# 436-300-001_Main_Power_Enclosure.net
KiCad netlist of a schematic drawn in EAGLE
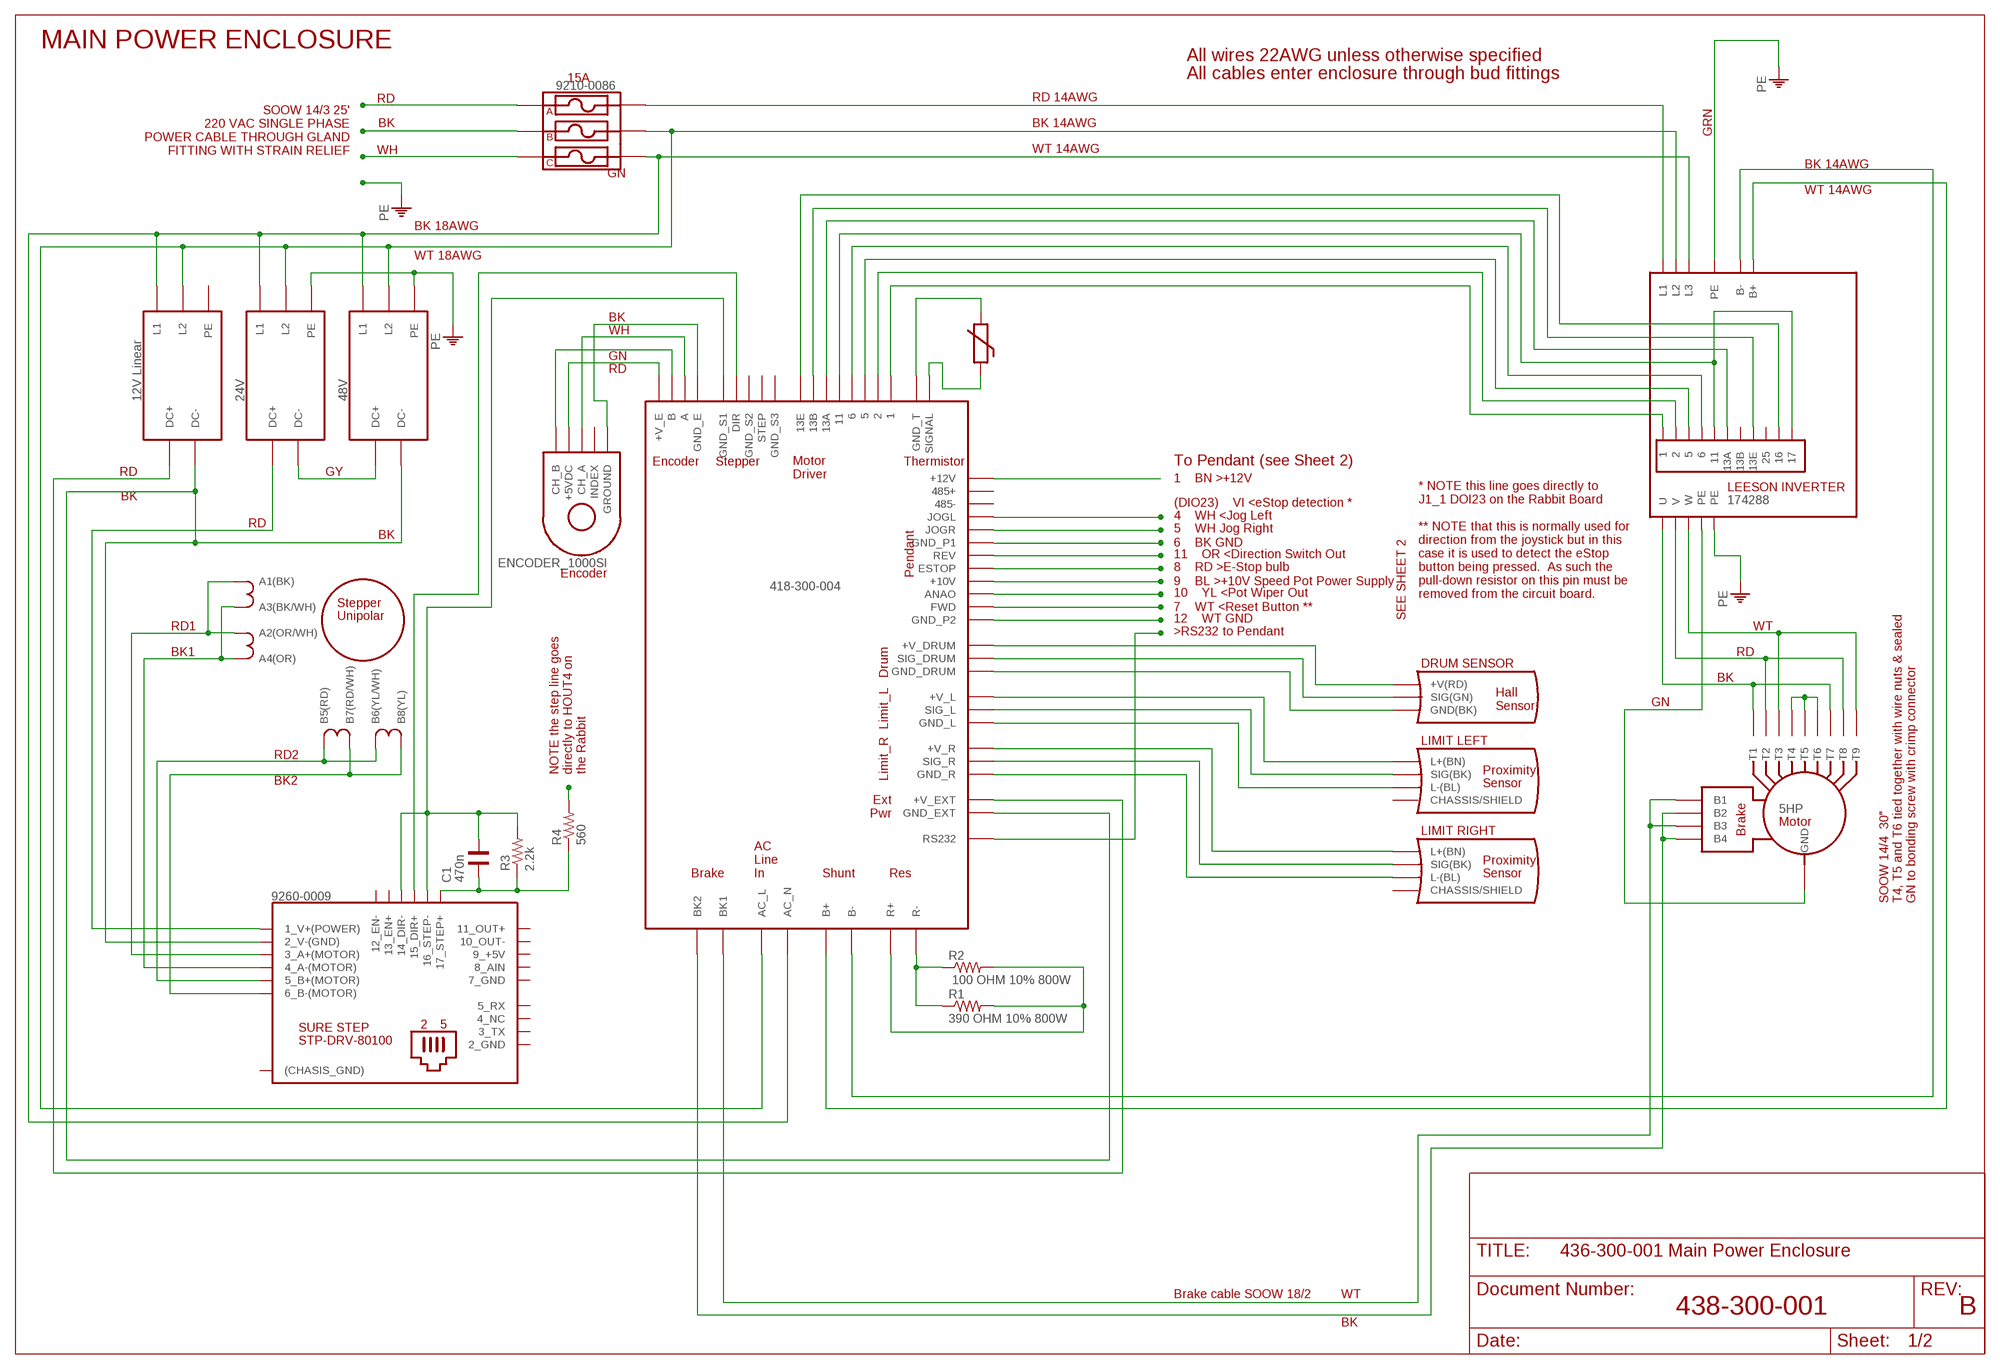
[diagram p0: schematic, sheet 1]
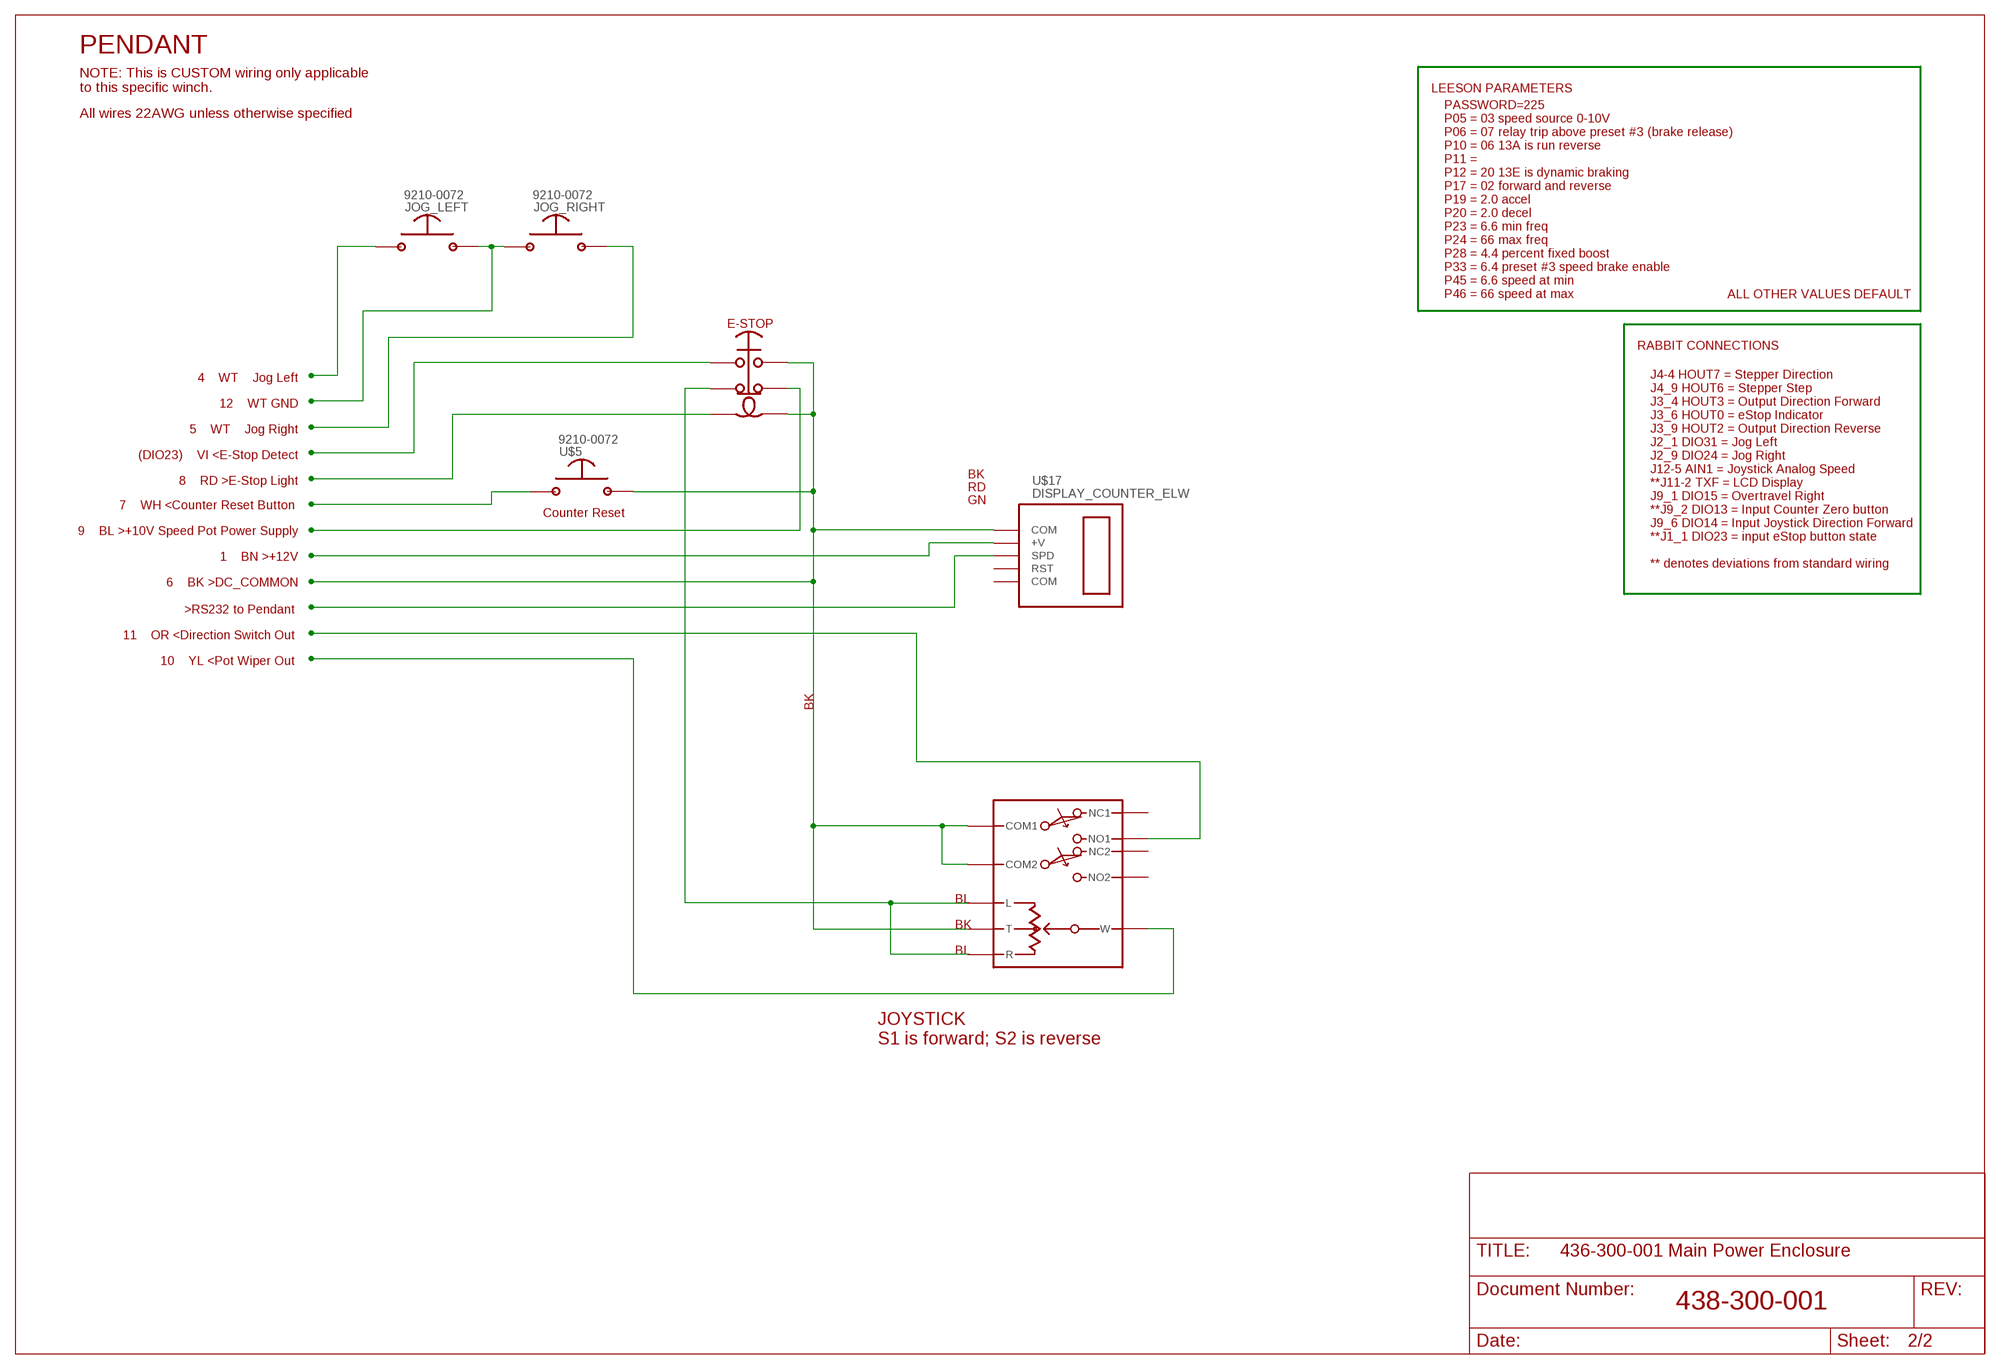
[diagram p1: schematic, sheet 2]

(export (version "E")
  (design (tool "Eeschema 10.0.6"))
  (components
    (comp (ref "JOG_LEFT")
      (value "Counter Reset")
      (footprint "eagle-import:BOGUS")
      (libsource (lib "eagle-import") (part "SWITCH_MOM_NO"))
    )
    (comp (ref "JOG_RIGHT")
      (value "Counter Reset")
      (footprint "eagle-import:BOGUS")
      (libsource (lib "eagle-import") (part "SWITCH_MOM_NO"))
    )
    (comp (ref "U$5")
      (value "Counter Reset")
      (footprint "eagle-import:BOGUS")
      (libsource (lib "eagle-import") (part "SWITCH_MOM_NO"))
    )
    (comp (ref "U$15")
      (value "SWITCH_ESTOP_LIGHTED")
      (footprint "eagle-import:BOGUS")
      (libsource (lib "eagle-import") (part "SWITCH_ESTOP_LIGHTED"))
    )
    (comp (ref "U$16")
      (value "JOYSTICK_PRO-5")
      (footprint "eagle-import:BOGUS")
      (libsource (lib "eagle-import") (part "JOYSTICK_PRO-5"))
    )
    (comp (ref "U$17")
      (value "DISPLAY_COUNTER_ELW")
      (footprint "eagle-import:BOGUS")
      (libsource (lib "eagle-import") (part "DISPLAY_COUNTER_ELW"))
    )
    (comp (ref "C1")
      (value "470n")
      (footprint "eagle-import:C0805")
      (libsource (lib "eagle-import") (part "C0805"))
    )
    (comp (ref "R1")
      (value "390 OHM 10% 800W")
      (footprint "eagle-import:AXIAL-0.3-KIT")
      (libsource (lib "eagle-import") (part "RESISTORKIT"))
    )
    (comp (ref "R2")
      (value "100 OHM 10% 800W")
      (footprint "eagle-import:AXIAL-0.3-KIT")
      (libsource (lib "eagle-import") (part "RESISTORKIT"))
    )
    (comp (ref "R3")
      (value "2.2k")
      (footprint "eagle-import:0805")
      (libsource (lib "eagle-import") (part "RESISTOR0805-RES"))
    )
    (comp (ref "R4")
      (value "560")
      (footprint "eagle-import:0805")
      (libsource (lib "eagle-import") (part "RESISTOR0805-RES"))
    )
    (comp (ref "U$1")
      (value "CONTROLLER_ECO_0.2")
      (footprint "eagle-import:BOGUS@2")
      (libsource (lib "eagle-import") (part "CONTROLLER_ECO_0.2"))
    )
    (comp (ref "U$2")
      (value "THERMISTOR")
      (footprint "eagle-import:BOGUS")
      (libsource (lib "eagle-import") (part "THERMISTOR"))
    )
    (comp (ref "U$3")
      (value "SENSOR_HALL")
      (footprint "eagle-import:BOGUS@1")
      (libsource (lib "eagle-import") (part "SENSOR_HALL"))
    )
    (comp (ref "U$4")
      (value "ENCODER_1000SI")
      (footprint "eagle-import:BOGUS")
      (libsource (lib "eagle-import") (part "ENCODER_1000SI"))
    )
    (comp (ref "U$6")
      (value "SENSOR_PROXIMITY")
      (footprint "eagle-import:BOGUS")
      (libsource (lib "eagle-import") (part "SENSOR_PROXIMITY"))
    )
    (comp (ref "U$7")
      (value "5HP")
      (footprint "eagle-import:BOGUS")
      (libsource (lib "eagle-import") (part "MOTOR_3PH"))
    )
    (comp (ref "U$8")
      (value "174288")
      (footprint "eagle-import:BOGUS@2")
      (libsource (lib "eagle-import") (part "INVERTER_LEESON_3-PHASE"))
    )
    (comp (ref "U$9")
      (value "SENSOR_PROXIMITY")
      (footprint "eagle-import:BOGUS")
      (libsource (lib "eagle-import") (part "SENSOR_PROXIMITY"))
    )
    (comp (ref "U$10")
      (value "24V")
      (footprint "eagle-import:BOGUS")
      (libsource (lib "eagle-import") (part "POWER_SUPPLY"))
    )
    (comp (ref "U$11")
      (value "FUSE_HOLDER_3-POLE")
      (footprint "eagle-import:BOGUS")
      (libsource (lib "eagle-import") (part "FUSE_HOLDER_3-POLE"))
    )
    (comp (ref "U$12")
      (value "48V")
      (footprint "eagle-import:BOGUS")
      (libsource (lib "eagle-import") (part "POWER_SUPPLY"))
    )
    (comp (ref "U$13")
      (value "MOTOR_STEPPER_UNIPOLAR")
      (footprint "eagle-import:BOGUS")
      (libsource (lib "eagle-import") (part "MOTOR_STEPPER_UNIPOLAR"))
    )
    (comp (ref "U$14")
      (value "SURE_STEP_STP-DRV-80100")
      (footprint "eagle-import:BOGUS")
      (libsource (lib "eagle-import") (part "SURE_STEP_STP-DRV-80100"))
    )
    (comp (ref "U$18")
      (value "12V Linear")
      (footprint "eagle-import:BOGUS")
      (libsource (lib "eagle-import") (part "POWER_SUPPLY"))
    )
  )
  (nets
    (net (code "1") (name "(CHASIS_GND)") (class "Default")
      (node (ref "U$14") (pin "P$1") (pinfunction "(CHASIS_GND)_P$1") (pintype "power_in"))
    )
    (net (code "2") (name "2_GND") (class "Default")
      (node (ref "U$14") (pin "P$19") (pinfunction "2_GND_P$19") (pintype "power_in"))
    )
    (net (code "3") (name "3_TX") (class "Default")
      (node (ref "U$14") (pin "P$20") (pinfunction "3_TX_P$20") (pintype "power_in"))
    )
    (net (code "4") (name "4_NC") (class "Default")
      (node (ref "U$14") (pin "P$21") (pinfunction "4_NC_P$21") (pintype "power_in"))
    )
    (net (code "5") (name "5_RX") (class "Default")
      (node (ref "U$14") (pin "P$22") (pinfunction "5_RX_P$22") (pintype "power_in"))
    )
    (net (code "6") (name "7_GND") (class "Default")
      (node (ref "U$14") (pin "P$8") (pinfunction "7_GND_P$8") (pintype "power_in"))
    )
    (net (code "7") (name "8_AIN") (class "Default")
      (node (ref "U$14") (pin "P$9") (pinfunction "8_AIN_P$9") (pintype "power_in"))
    )
    (net (code "8") (name "9_+5V") (class "Default")
      (node (ref "U$14") (pin "P$10") (pinfunction "9_+5V_P$10") (pintype "power_in"))
    )
    (net (code "9") (name "10_OUT-") (class "Default")
      (node (ref "U$14") (pin "P$11") (pinfunction "10_OUT-_P$11") (pintype "power_in"))
    )
    (net (code "10") (name "11_OUT+") (class "Default")
      (node (ref "U$14") (pin "P$12") (pinfunction "11_OUT+_P$12") (pintype "power_in"))
    )
    (net (code "11") (name "12_EN-") (class "Default")
      (node (ref "U$14") (pin "P$13") (pinfunction "12_EN-_P$13") (pintype "power_in"))
    )
    (net (code "12") (name "13_EN+") (class "Default")
      (node (ref "U$14") (pin "P$14") (pinfunction "13_EN+_P$14") (pintype "power_in"))
    )
    (net (code "13") (name "Net-(JOG_LEFT-PadP$2)") (class "Default")
      (node (ref "JOG_LEFT") (pin "P$2") (pinfunction "P$2_P$2") (pintype "bidirectional"))
      (node (ref "JOG_RIGHT") (pin "P$1") (pinfunction "P$1_P$1") (pintype "bidirectional"))
    )
    (net (code "14") (name "Net-(R1-1)") (class "Default")
      (node (ref "R1") (pin "P$1") (pinfunction "1_P$1") (pintype "passive"))
      (node (ref "R2") (pin "P$1") (pinfunction "1_P$1") (pintype "passive"))
      (node (ref "U$1") (pin "P$44") (pinfunction "R-_P$44") (pintype "bidirectional"))
    )
    (net (code "15") (name "Net-(R1-2)") (class "Default")
      (node (ref "R1") (pin "P$2") (pinfunction "2_P$2") (pintype "passive"))
      (node (ref "R2") (pin "P$2") (pinfunction "2_P$2") (pintype "passive"))
      (node (ref "U$1") (pin "P$43") (pinfunction "R+_P$43") (pintype "bidirectional"))
    )
    (net (code "16") (name "Net-(U$1-+V_DRUM)") (class "Default")
      (node (ref "U$1") (pin "P$3") (pinfunction "+V_DRUM_P$3") (pintype "bidirectional"))
      (node (ref "U$3") (pin "P$1") (pinfunction "+V(RD)_P$1") (pintype "bidirectional"))
    )
    (net (code "17") (name "Net-(U$1-+V_E)") (class "Default")
      (node (ref "U$1") (pin "P$4") (pinfunction "+V_E_P$4") (pintype "bidirectional"))
      (node (ref "U$4") (pin "P$1") (pinfunction "+5VDC_P$1") (pintype "bidirectional"))
    )
    (net (code "18") (name "Net-(U$1-+V_EXT)") (class "Default")
      (node (ref "U$1") (pin "P$5") (pinfunction "+V_EXT_P$5") (pintype "bidirectional"))
      (node (ref "U$18") (pin "P$1") (pinfunction "DC+_P$1") (pintype "bidirectional"))
    )
    (net (code "19") (name "Net-(U$1-+V_L)") (class "Default")
      (node (ref "U$1") (pin "P$6") (pinfunction "+V_L_P$6") (pintype "bidirectional"))
      (node (ref "U$6") (pin "P$2") (pinfunction "L+(BN)_P$2") (pintype "bidirectional"))
    )
    (net (code "20") (name "Net-(U$1-+V_R)") (class "Default")
      (node (ref "U$1") (pin "P$7") (pinfunction "+V_R_P$7") (pintype "bidirectional"))
      (node (ref "U$9") (pin "P$2") (pinfunction "L+(BN)_P$2") (pintype "bidirectional"))
    )
    (net (code "21") (name "Net-(U$1-1)") (class "Default")
      (node (ref "U$1") (pin "P$8") (pinfunction "1_P$8") (pintype "bidirectional"))
      (node (ref "U$8") (pin "P$1") (pinfunction "1_P$1") (pintype "bidirectional"))
    )
    (net (code "22") (name "Net-(U$1-2)") (class "Default")
      (node (ref "U$1") (pin "P$9") (pinfunction "2_P$9") (pintype "bidirectional"))
      (node (ref "U$8") (pin "P$2") (pinfunction "2_P$2") (pintype "bidirectional"))
    )
    (net (code "23") (name "Net-(U$1-5)") (class "Default")
      (node (ref "U$1") (pin "P$10") (pinfunction "5_P$10") (pintype "bidirectional"))
      (node (ref "U$8") (pin "P$3") (pinfunction "5_P$3") (pintype "bidirectional"))
    )
    (net (code "24") (name "Net-(U$1-6)") (class "Default")
      (node (ref "U$1") (pin "P$11") (pinfunction "6_P$11") (pintype "bidirectional"))
      (node (ref "U$8") (pin "P$4") (pinfunction "6_P$4") (pintype "bidirectional"))
    )
    (net (code "25") (name "Net-(U$1-11)") (class "Default")
      (node (ref "U$1") (pin "P$12") (pinfunction "11_P$12") (pintype "bidirectional"))
      (node (ref "U$8") (pin "P$10") (pinfunction "17_P$10") (pintype "bidirectional"))
      (node (ref "U$8") (pin "P$5") (pinfunction "11_P$5") (pintype "bidirectional"))
    )
    (net (code "26") (name "Net-(U$1-13A)") (class "Default")
      (node (ref "U$1") (pin "P$13") (pinfunction "13A_P$13") (pintype "bidirectional"))
      (node (ref "U$8") (pin "P$6") (pinfunction "13A_P$6") (pintype "bidirectional"))
    )
    (net (code "27") (name "Net-(U$1-13B)") (class "Default")
      (node (ref "U$1") (pin "P$14") (pinfunction "13B_P$14") (pintype "bidirectional"))
      (node (ref "U$8") (pin "P$8") (pinfunction "13E_P$8") (pintype "bidirectional"))
    )
    (net (code "28") (name "Net-(U$1-13E)") (class "Default")
      (node (ref "U$1") (pin "P$15") (pinfunction "13E_P$15") (pintype "bidirectional"))
      (node (ref "U$8") (pin "P$9") (pinfunction "16_P$9") (pintype "bidirectional"))
    )
    (net (code "29") (name "Net-(U$1-A)") (class "Default")
      (node (ref "U$1") (pin "P$18") (pinfunction "A_P$18") (pintype "bidirectional"))
      (node (ref "U$4") (pin "P$2") (pinfunction "CH_A_P$2") (pintype "bidirectional"))
    )
    (net (code "30") (name "Net-(U$1-AC_L)") (class "Default")
      (node (ref "U$1") (pin "P$19") (pinfunction "AC_L_P$19") (pintype "bidirectional"))
      (node (ref "U$10") (pin "P$4") (pinfunction "L2_P$4") (pintype "bidirectional"))
      (node (ref "U$11") (pin "P$4") (pinfunction "P$4_P$4") (pintype "bidirectional"))
      (node (ref "U$12") (pin "P$4") (pinfunction "L2_P$4") (pintype "bidirectional"))
      (node (ref "U$18") (pin "P$4") (pinfunction "L2_P$4") (pintype "bidirectional"))
      (node (ref "U$8") (pin "P$15") (pinfunction "L2_P$15") (pintype "power_in"))
    )
    (net (code "31") (name "Net-(U$1-AC_N)") (class "Default")
      (node (ref "U$1") (pin "P$20") (pinfunction "AC_N_P$20") (pintype "bidirectional"))
      (node (ref "U$10") (pin "P$3") (pinfunction "L1_P$3") (pintype "bidirectional"))
      (node (ref "U$11") (pin "P$6") (pinfunction "P$6_P$6") (pintype "bidirectional"))
      (node (ref "U$12") (pin "P$3") (pinfunction "L1_P$3") (pintype "bidirectional"))
      (node (ref "U$18") (pin "P$3") (pinfunction "L1_P$3") (pintype "bidirectional"))
      (node (ref "U$8") (pin "P$16") (pinfunction "L3_P$16") (pintype "power_in"))
    )
    (net (code "32") (name "Net-(U$1-B)") (class "Default")
      (node (ref "U$1") (pin "P$22") (pinfunction "B_P$22") (pintype "bidirectional"))
      (node (ref "U$4") (pin "P$3") (pinfunction "CH_B_P$3") (pintype "bidirectional"))
    )
    (net (code "33") (name "Net-(U$1-B+)") (class "Default")
      (node (ref "U$1") (pin "P$23") (pinfunction "B+_P$23") (pintype "bidirectional"))
      (node (ref "U$8") (pin "P$12") (pinfunction "B+_P$12") (pintype "bidirectional"))
    )
    (net (code "34") (name "Net-(U$1-B-)") (class "Default")
      (node (ref "U$1") (pin "P$24") (pinfunction "B-_P$24") (pintype "bidirectional"))
      (node (ref "U$8") (pin "P$13") (pinfunction "B-_P$13") (pintype "bidirectional"))
    )
    (net (code "35") (name "Net-(U$1-BK1)") (class "Default")
      (node (ref "U$1") (pin "P$25") (pinfunction "BK1_P$25") (pintype "bidirectional"))
      (node (ref "U$7") (pin "P$1") (pinfunction "B1_P$1") (pintype "bidirectional"))
      (node (ref "U$7") (pin "P$3") (pinfunction "B3_P$3") (pintype "bidirectional"))
    )
    (net (code "36") (name "Net-(U$1-BK2)") (class "Default")
      (node (ref "U$1") (pin "P$26") (pinfunction "BK2_P$26") (pintype "bidirectional"))
      (node (ref "U$7") (pin "P$2") (pinfunction "B2_P$2") (pintype "bidirectional"))
      (node (ref "U$7") (pin "P$4") (pinfunction "B4_P$4") (pintype "bidirectional"))
    )
    (net (code "37") (name "Net-(U$1-DIR)") (class "Default")
      (node (ref "U$1") (pin "P$27") (pinfunction "DIR_P$27") (pintype "bidirectional"))
      (node (ref "U$14") (pin "P$16") (pinfunction "15_DIR+_P$16") (pintype "power_in"))
    )
    (net (code "38") (name "Net-(U$1-GND_DRUM)") (class "Default")
      (node (ref "U$1") (pin "P$30") (pinfunction "GND_DRUM_P$30") (pintype "bidirectional"))
      (node (ref "U$3") (pin "P$2") (pinfunction "GND(BK)_P$2") (pintype "bidirectional"))
    )
    (net (code "39") (name "Net-(U$1-GND_E)") (class "Default")
      (node (ref "U$1") (pin "P$31") (pinfunction "GND_E_P$31") (pintype "bidirectional"))
      (node (ref "U$4") (pin "P$4") (pinfunction "GROUND_P$4") (pintype "bidirectional"))
    )
    (net (code "40") (name "Net-(U$1-GND_EXT)") (class "Default")
      (node (ref "U$1") (pin "P$32") (pinfunction "GND_EXT_P$32") (pintype "bidirectional"))
      (node (ref "U$12") (pin "P$2") (pinfunction "DC-_P$2") (pintype "bidirectional"))
      (node (ref "U$14") (pin "P$3") (pinfunction "2_V-(GND)_P$3") (pintype "power_in"))
      (node (ref "U$18") (pin "P$2") (pinfunction "DC-_P$2") (pintype "bidirectional"))
    )
    (net (code "41") (name "Net-(U$1-GND_L)") (class "Default")
      (node (ref "U$1") (pin "P$33") (pinfunction "GND_L_P$33") (pintype "bidirectional"))
      (node (ref "U$6") (pin "P$3") (pinfunction "L-(BL)_P$3") (pintype "bidirectional"))
    )
    (net (code "42") (name "Net-(U$1-GND_R)") (class "Default")
      (node (ref "U$1") (pin "P$36") (pinfunction "GND_R_P$36") (pintype "bidirectional"))
      (node (ref "U$9") (pin "P$3") (pinfunction "L-(BL)_P$3") (pintype "bidirectional"))
    )
    (net (code "43") (name "Net-(U$1-GND_S1)") (class "Default")
      (node (ref "C1") (pin "2") (pinfunction "2_2") (pintype "passive"))
      (node (ref "R3") (pin "2") (pinfunction "2_2") (pintype "passive"))
      (node (ref "U$1") (pin "P$37") (pinfunction "GND_S1_P$37") (pintype "bidirectional"))
      (node (ref "U$14") (pin "P$15") (pinfunction "14_DIR-_P$15") (pintype "power_in"))
      (node (ref "U$14") (pin "P$17") (pinfunction "16_STEP-_P$17") (pintype "power_in"))
    )
    (net (code "44") (name "Net-(U$1-GND_T)") (class "Default")
      (node (ref "U$1") (pin "P$40") (pinfunction "GND_T_P$40") (pintype "bidirectional"))
      (node (ref "U$2") (pin "P$1") (pinfunction "P$1_P$1") (pintype "bidirectional"))
    )
    (net (code "45") (name "Net-(U$1-SIGNAL)") (class "Default")
      (node (ref "U$1") (pin "P$47") (pinfunction "SIGNAL_P$47") (pintype "bidirectional"))
      (node (ref "U$2") (pin "P$2") (pinfunction "P$2_P$2") (pintype "bidirectional"))
    )
    (net (code "46") (name "Net-(U$1-SIG_DRUM)") (class "Default")
      (node (ref "U$1") (pin "P$48") (pinfunction "SIG_DRUM_P$48") (pintype "bidirectional"))
      (node (ref "U$3") (pin "P$3") (pinfunction "SIG(GN)_P$3") (pintype "bidirectional"))
    )
    (net (code "47") (name "Net-(U$1-SIG_L)") (class "Default")
      (node (ref "U$1") (pin "P$49") (pinfunction "SIG_L_P$49") (pintype "bidirectional"))
      (node (ref "U$6") (pin "P$4") (pinfunction "SIG(BK)_P$4") (pintype "bidirectional"))
    )
    (net (code "48") (name "Net-(U$1-SIG_R)") (class "Default")
      (node (ref "U$1") (pin "P$50") (pinfunction "SIG_R_P$50") (pintype "bidirectional"))
      (node (ref "U$9") (pin "P$4") (pinfunction "SIG(BK)_P$4") (pintype "bidirectional"))
    )
    (net (code "49") (name "Net-(U$7-GND)") (class "Default")
      (node (ref "U$7") (pin "P$14") (pinfunction "GND_P$14") (pintype "bidirectional"))
      (node (ref "U$8") (pin "P$18") (pinfunction "PE_P$18") (pintype "power_in"))
    )
    (net (code "50") (name "Net-(U$7-T1)") (class "Default")
      (node (ref "U$7") (pin "P$11") (pinfunction "T7_P$11") (pintype "bidirectional"))
      (node (ref "U$7") (pin "P$5") (pinfunction "T1_P$5") (pintype "bidirectional"))
      (node (ref "U$8") (pin "P$20") (pinfunction "U_P$20") (pintype "power_in"))
    )
    (net (code "51") (name "Net-(U$7-T2)") (class "Default")
      (node (ref "U$7") (pin "P$12") (pinfunction "T8_P$12") (pintype "bidirectional"))
      (node (ref "U$7") (pin "P$6") (pinfunction "T2_P$6") (pintype "bidirectional"))
      (node (ref "U$8") (pin "P$21") (pinfunction "V_P$21") (pintype "power_in"))
    )
    (net (code "52") (name "Net-(U$7-T3)") (class "Default")
      (node (ref "U$7") (pin "P$13") (pinfunction "T9_P$13") (pintype "bidirectional"))
      (node (ref "U$7") (pin "P$7") (pinfunction "T3_P$7") (pintype "bidirectional"))
      (node (ref "U$8") (pin "P$22") (pinfunction "W_P$22") (pintype "power_in"))
    )
    (net (code "53") (name "Net-(U$7-T4)") (class "Default")
      (node (ref "U$7") (pin "P$10") (pinfunction "T6_P$10") (pintype "bidirectional"))
      (node (ref "U$7") (pin "P$8") (pinfunction "T4_P$8") (pintype "bidirectional"))
      (node (ref "U$7") (pin "P$9") (pinfunction "T5_P$9") (pintype "bidirectional"))
    )
    (net (code "54") (name "Net-(U$8-L1)") (class "Default")
      (node (ref "U$11") (pin "P$3") (pinfunction "P$3_P$3") (pintype "bidirectional"))
      (node (ref "U$8") (pin "P$14") (pinfunction "L1_P$14") (pintype "power_in"))
    )
    (net (code "55") (name "Net-(U$10-DC+)") (class "Default")
      (node (ref "U$10") (pin "P$1") (pinfunction "DC+_P$1") (pintype "bidirectional"))
      (node (ref "U$14") (pin "P$2") (pinfunction "1_V+(POWER)_P$2") (pintype "power_in"))
    )
    (net (code "56") (name "Net-(U$10-DC-)") (class "Default")
      (node (ref "U$10") (pin "P$2") (pinfunction "DC-_P$2") (pintype "bidirectional"))
      (node (ref "U$12") (pin "P$1") (pinfunction "DC+_P$1") (pintype "bidirectional"))
    )
    (net (code "57") (name "Net-(U$13-A1(BK))") (class "Default")
      (node (ref "U$13") (pin "P$1") (pinfunction "A1(BK)_P$1") (pintype "bidirectional"))
      (node (ref "U$13") (pin "P$2") (pinfunction "A2(OR/WH)_P$2") (pintype "bidirectional"))
      (node (ref "U$14") (pin "P$4") (pinfunction "3_A+(MOTOR)_P$4") (pintype "power_in"))
    )
    (net (code "58") (name "Net-(U$13-A3(BK{slash}WH))") (class "Default")
      (node (ref "U$13") (pin "P$3") (pinfunction "A3(BK/WH)_P$3") (pintype "bidirectional"))
      (node (ref "U$13") (pin "P$4") (pinfunction "A4(OR)_P$4") (pintype "bidirectional"))
      (node (ref "U$14") (pin "P$5") (pinfunction "4_A-(MOTOR)_P$5") (pintype "power_in"))
    )
    (net (code "59") (name "Net-(U$13-B5(RD))") (class "Default")
      (node (ref "U$13") (pin "P$5") (pinfunction "B5(RD)_P$5") (pintype "bidirectional"))
      (node (ref "U$13") (pin "P$6") (pinfunction "B6(YL/WH)_P$6") (pintype "bidirectional"))
      (node (ref "U$14") (pin "P$6") (pinfunction "5_B+(MOTOR)_P$6") (pintype "power_in"))
    )
    (net (code "60") (name "Net-(U$13-B7(RD{slash}WH))") (class "Default")
      (node (ref "U$13") (pin "P$7") (pinfunction "B7(RD/WH)_P$7") (pintype "bidirectional"))
      (node (ref "U$13") (pin "P$8") (pinfunction "B8(YL)_P$8") (pintype "bidirectional"))
      (node (ref "U$14") (pin "P$7") (pinfunction "6_B-(MOTOR)_P$7") (pintype "power_in"))
    )
    (net (code "61") (name "Net-(U$14-17_STEP+)") (class "Default")
      (node (ref "C1") (pin "1") (pinfunction "1_1") (pintype "passive"))
      (node (ref "R3") (pin "1") (pinfunction "1_1") (pintype "passive"))
      (node (ref "R4") (pin "1") (pinfunction "1_1") (pintype "passive"))
      (node (ref "U$14") (pin "P$18") (pinfunction "17_STEP+_P$18") (pintype "power_in"))
    )
    (net (code "62") (name "Net-(U$16-COM1)") (class "Default")
      (node (ref "U$15") (pin "P$3") (pinfunction "P$3_P$3") (pintype "bidirectional"))
      (node (ref "U$15") (pin "P$6") (pinfunction "P$6_P$6") (pintype "bidirectional"))
      (node (ref "U$16") (pin "P$1") (pinfunction "COM1_P$1") (pintype "bidirectional"))
      (node (ref "U$16") (pin "P$2") (pinfunction "COM2_P$2") (pintype "bidirectional"))
      (node (ref "U$16") (pin "P$9") (pinfunction "T_P$9") (pintype "bidirectional"))
      (node (ref "U$17") (pin "P$2") (pinfunction "COM_P$2") (pintype "bidirectional"))
      (node (ref "U$5") (pin "P$2") (pinfunction "P$2_P$2") (pintype "bidirectional"))
    )
    (net (code "63") (name "Net-(U$16-L)") (class "Default")
      (node (ref "U$15") (pin "P$2") (pinfunction "P$2_P$2") (pintype "bidirectional"))
      (node (ref "U$16") (pin "P$3") (pinfunction "L_P$3") (pintype "bidirectional"))
      (node (ref "U$16") (pin "P$8") (pinfunction "R_P$8") (pintype "bidirectional"))
    )
    (net (code "64") (name "PE") (class "Default")
      (node (ref "U$10") (pin "P$5") (pinfunction "PE_P$5") (pintype "bidirectional"))
      (node (ref "U$12") (pin "P$5") (pinfunction "PE_P$5") (pintype "bidirectional"))
      (node (ref "U$8") (pin "P$17") (pinfunction "PE_P$17") (pintype "power_in"))
      (node (ref "U$8") (pin "P$19") (pinfunction "PE_P$19") (pintype "power_in"))
    )
    (net (code "65") (name "unconnected-(JOG_LEFT-PadP$1)") (class "Default")
      (node (ref "JOG_LEFT") (pin "P$1") (pinfunction "P$1_P$1") (pintype "bidirectional"))
    )
    (net (code "66") (name "unconnected-(JOG_RIGHT-PadP$2)") (class "Default")
      (node (ref "JOG_RIGHT") (pin "P$2") (pinfunction "P$2_P$2") (pintype "bidirectional"))
    )
    (net (code "67") (name "unconnected-(R4-Pad2)") (class "Default")
      (node (ref "R4") (pin "2") (pinfunction "2_2") (pintype "passive"))
    )
    (net (code "68") (name "unconnected-(U$1-+10V-PadP$1)") (class "Default")
      (node (ref "U$1") (pin "P$1") (pinfunction "+10V_P$1") (pintype "bidirectional"))
    )
    (net (code "69") (name "unconnected-(U$1-+12V-PadP$2)") (class "Default")
      (node (ref "U$1") (pin "P$2") (pinfunction "+12V_P$2") (pintype "bidirectional"))
    )
    (net (code "70") (name "unconnected-(U$1-485+-PadP$16)") (class "Default")
      (node (ref "U$1") (pin "P$16") (pinfunction "485+_P$16") (pintype "bidirectional"))
    )
    (net (code "71") (name "unconnected-(U$1-485--PadP$17)") (class "Default")
      (node (ref "U$1") (pin "P$17") (pinfunction "485-_P$17") (pintype "bidirectional"))
    )
    (net (code "72") (name "unconnected-(U$1-ANAO-PadP$21)") (class "Default")
      (node (ref "U$1") (pin "P$21") (pinfunction "ANAO_P$21") (pintype "bidirectional"))
    )
    (net (code "73") (name "unconnected-(U$1-ESTOP-PadP$28)") (class "Default")
      (node (ref "U$1") (pin "P$28") (pinfunction "ESTOP_P$28") (pintype "bidirectional"))
    )
    (net (code "74") (name "unconnected-(U$1-FWD-PadP$29)") (class "Default")
      (node (ref "U$1") (pin "P$29") (pinfunction "FWD_P$29") (pintype "bidirectional"))
    )
    (net (code "75") (name "unconnected-(U$1-GND_P1-PadP$34)") (class "Default")
      (node (ref "U$1") (pin "P$34") (pinfunction "GND_P1_P$34") (pintype "bidirectional"))
    )
    (net (code "76") (name "unconnected-(U$1-GND_P2-PadP$35)") (class "Default")
      (node (ref "U$1") (pin "P$35") (pinfunction "GND_P2_P$35") (pintype "bidirectional"))
    )
    (net (code "77") (name "unconnected-(U$1-GND_S2-PadP$38)") (class "Default")
      (node (ref "U$1") (pin "P$38") (pinfunction "GND_S2_P$38") (pintype "bidirectional"))
    )
    (net (code "78") (name "unconnected-(U$1-GND_S3-PadP$39)") (class "Default")
      (node (ref "U$1") (pin "P$39") (pinfunction "GND_S3_P$39") (pintype "bidirectional"))
    )
    (net (code "79") (name "unconnected-(U$1-JOGL-PadP$41)") (class "Default")
      (node (ref "U$1") (pin "P$41") (pinfunction "JOGL_P$41") (pintype "bidirectional"))
    )
    (net (code "80") (name "unconnected-(U$1-JOGR-PadP$42)") (class "Default")
      (node (ref "U$1") (pin "P$42") (pinfunction "JOGR_P$42") (pintype "bidirectional"))
    )
    (net (code "81") (name "unconnected-(U$1-REV-PadP$45)") (class "Default")
      (node (ref "U$1") (pin "P$45") (pinfunction "REV_P$45") (pintype "bidirectional"))
    )
    (net (code "82") (name "unconnected-(U$1-RS232-PadP$46)") (class "Default")
      (node (ref "U$1") (pin "P$46") (pinfunction "RS232_P$46") (pintype "bidirectional"))
    )
    (net (code "83") (name "unconnected-(U$1-STEP-PadP$51)") (class "Default")
      (node (ref "U$1") (pin "P$51") (pinfunction "STEP_P$51") (pintype "bidirectional"))
    )
    (net (code "84") (name "unconnected-(U$4-INDEX-PadP$5)") (class "Default")
      (node (ref "U$4") (pin "P$5") (pinfunction "INDEX_P$5") (pintype "bidirectional"))
    )
    (net (code "85") (name "unconnected-(U$5-PadP$1)") (class "Default")
      (node (ref "U$5") (pin "P$1") (pinfunction "P$1_P$1") (pintype "bidirectional"))
    )
    (net (code "86") (name "unconnected-(U$6-CHASSIS{slash}SHIELD-PadP$1)") (class "Default")
      (node (ref "U$6") (pin "P$1") (pinfunction "CHASSIS/SHIELD_P$1") (pintype "bidirectional"))
    )
    (net (code "87") (name "unconnected-(U$8-13B-PadP$7)") (class "Default")
      (node (ref "U$8") (pin "P$7") (pinfunction "13B_P$7") (pintype "bidirectional"))
    )
    (net (code "88") (name "unconnected-(U$8-25-PadP$11)") (class "Default")
      (node (ref "U$8") (pin "P$11") (pinfunction "25_P$11") (pintype "bidirectional"))
    )
    (net (code "89") (name "unconnected-(U$9-CHASSIS{slash}SHIELD-PadP$1)") (class "Default")
      (node (ref "U$9") (pin "P$1") (pinfunction "CHASSIS/SHIELD_P$1") (pintype "bidirectional"))
    )
    (net (code "90") (name "unconnected-(U$11-PadP$1)") (class "Default")
      (node (ref "U$11") (pin "P$1") (pinfunction "P$1_P$1") (pintype "bidirectional"))
    )
    (net (code "91") (name "unconnected-(U$11-PadP$2)") (class "Default")
      (node (ref "U$11") (pin "P$2") (pinfunction "P$2_P$2") (pintype "bidirectional"))
    )
    (net (code "92") (name "unconnected-(U$11-PadP$5)") (class "Default")
      (node (ref "U$11") (pin "P$5") (pinfunction "P$5_P$5") (pintype "bidirectional"))
    )
    (net (code "93") (name "unconnected-(U$15-PadP$1)") (class "Default")
      (node (ref "U$15") (pin "P$1") (pinfunction "P$1_P$1") (pintype "bidirectional"))
    )
    (net (code "94") (name "unconnected-(U$15-PadP$4)") (class "Default")
      (node (ref "U$15") (pin "P$4") (pinfunction "P$4_P$4") (pintype "bidirectional"))
    )
    (net (code "95") (name "unconnected-(U$15-PadP$5)") (class "Default")
      (node (ref "U$15") (pin "P$5") (pinfunction "P$5_P$5") (pintype "bidirectional"))
    )
    (net (code "96") (name "unconnected-(U$16-NC1-PadP$4)") (class "Default")
      (node (ref "U$16") (pin "P$4") (pinfunction "NC1_P$4") (pintype "bidirectional"))
    )
    (net (code "97") (name "unconnected-(U$16-NC2-PadP$5)") (class "Default")
      (node (ref "U$16") (pin "P$5") (pinfunction "NC2_P$5") (pintype "bidirectional"))
    )
    (net (code "98") (name "unconnected-(U$16-NO1-PadP$6)") (class "Default")
      (node (ref "U$16") (pin "P$6") (pinfunction "NO1_P$6") (pintype "bidirectional"))
    )
    (net (code "99") (name "unconnected-(U$16-NO2-PadP$7)") (class "Default")
      (node (ref "U$16") (pin "P$7") (pinfunction "NO2_P$7") (pintype "bidirectional"))
    )
    (net (code "100") (name "unconnected-(U$16-W-PadP$10)") (class "Default")
      (node (ref "U$16") (pin "P$10") (pinfunction "W_P$10") (pintype "bidirectional"))
    )
    (net (code "101") (name "unconnected-(U$17-+V-PadP$1)") (class "Default")
      (node (ref "U$17") (pin "P$1") (pinfunction "+V_P$1") (pintype "bidirectional"))
    )
    (net (code "102") (name "unconnected-(U$17-COM-PadP$3)") (class "Default")
      (node (ref "U$17") (pin "P$3") (pinfunction "COM_P$3") (pintype "bidirectional"))
    )
    (net (code "103") (name "unconnected-(U$17-RST-PadP$4)") (class "Default")
      (node (ref "U$17") (pin "P$4") (pinfunction "RST_P$4") (pintype "bidirectional"))
    )
    (net (code "104") (name "unconnected-(U$17-SPD-PadP$5)") (class "Default")
      (node (ref "U$17") (pin "P$5") (pinfunction "SPD_P$5") (pintype "bidirectional"))
    )
    (net (code "105") (name "unconnected-(U$18-PE-PadP$5)") (class "Default")
      (node (ref "U$18") (pin "P$5") (pinfunction "PE_P$5") (pintype "bidirectional"))
    )
  )
)
